# weatherstation.net
KiCad netlist of a schematic drawn in Altium Designer
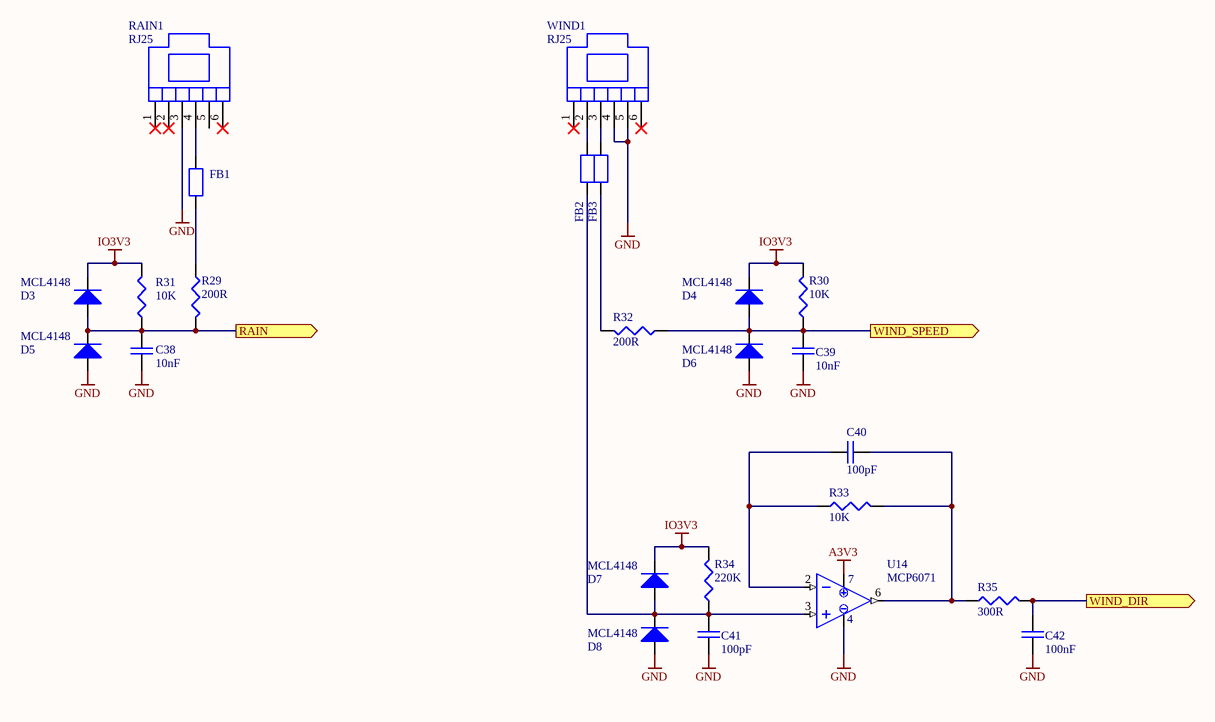
[diagram p0: weatherstation.SchDoc]

(export (version "E")
  (design (tool "Eeschema 10.0.6"))
  (components
    (comp (ref "C38")
      (value "10nF")
      (footprint "0603")
      (description "Capacitor")
      (fields (field (name "OWNER") "Nuno Brum"))
      (libsource (lib "Alcetronics_Devices") (part "CAP"))
    )
    (comp (ref "C39")
      (value "10nF")
      (footprint "0603")
      (description "Capacitor")
      (fields (field (name "OWNER") "Nuno Brum"))
      (libsource (lib "Alcetronics_Devices") (part "CAP"))
    )
    (comp (ref "C40")
      (value "100pF")
      (footprint "0603")
      (description "Capacitor")
      (fields (field (name "OWNER") "Nuno Brum"))
      (libsource (lib "Alcetronics_Devices") (part "CAP"))
    )
    (comp (ref "C41")
      (value "100pF")
      (footprint "0603")
      (description "Capacitor")
      (fields (field (name "OWNER") "Nuno Brum"))
      (libsource (lib "Alcetronics_Devices") (part "CAP"))
    )
    (comp (ref "C42")
      (value "100nF")
      (footprint "0603")
      (description "Capacitor")
      (fields (field (name "OWNER") "Nuno Brum"))
      (libsource (lib "Alcetronics_Devices") (part "CAP"))
    )
    (comp (ref "D3")
      (value "MCL4148")
      (footprint "0805@DIODE")
      (description "Vishay Standard Avalanche Sinterglass Diode")
      (fields (field (name "OWNER") "Nuno Brum"))
      (libsource (lib "Alcetronics_Devices") (part "Diode"))
    )
    (comp (ref "D4")
      (value "MCL4148")
      (footprint "0805@DIODE")
      (description "Vishay Standard Avalanche Sinterglass Diode")
      (fields (field (name "OWNER") "Nuno Brum"))
      (libsource (lib "Alcetronics_Devices") (part "Diode"))
    )
    (comp (ref "D5")
      (value "MCL4148")
      (footprint "0805@DIODE")
      (description "Vishay Standard Avalanche Sinterglass Diode")
      (fields (field (name "OWNER") "Nuno Brum"))
      (libsource (lib "Alcetronics_Devices") (part "Diode"))
    )
    (comp (ref "D6")
      (value "MCL4148")
      (footprint "0805@DIODE")
      (description "Vishay Standard Avalanche Sinterglass Diode")
      (fields (field (name "OWNER") "Nuno Brum"))
      (libsource (lib "Alcetronics_Devices") (part "Diode"))
    )
    (comp (ref "D7")
      (value "MCL4148")
      (footprint "0805@DIODE")
      (description "Vishay Standard Avalanche Sinterglass Diode")
      (fields (field (name "OWNER") "Nuno Brum"))
      (libsource (lib "Alcetronics_Devices") (part "Diode"))
    )
    (comp (ref "D8")
      (value "MCL4148")
      (footprint "0805@DIODE")
      (description "Vishay Standard Avalanche Sinterglass Diode")
      (fields (field (name "OWNER") "Nuno Brum"))
      (libsource (lib "Alcetronics_Devices") (part "Diode"))
    )
    (comp (ref "FB1")
      (value "150Z_100MHz")
      (footprint "0805")
      (description "Ferrite bead")
      (fields (field (name "OWNER") "Sergio Pires"))
      (libsource (lib "Alcetronics_Devices") (part "FERRITE-BEAD-AXIAL"))
    )
    (comp (ref "FB2")
      (value "150Z_100MHz")
      (footprint "0805")
      (description "Ferrite bead")
      (fields (field (name "OWNER") "Sergio Pires"))
      (libsource (lib "Alcetronics_Devices") (part "FERRITE-BEAD-AXIAL"))
    )
    (comp (ref "FB3")
      (value "150Z_100MHz")
      (footprint "0805")
      (description "Ferrite bead")
      (fields (field (name "OWNER") "Sergio Pires"))
      (libsource (lib "Alcetronics_Devices") (part "FERRITE-BEAD-AXIAL"))
    )
    (comp (ref "R29")
      (value "200R")
      (footprint "0603")
      (description "Resistor")
      (fields (field (name "OWNER") "Nuno Brum"))
      (libsource (lib "Alcetronics_Devices") (part "RES"))
    )
    (comp (ref "R30")
      (value "10K")
      (footprint "0603")
      (description "Resistor")
      (fields (field (name "OWNER") "Nuno Brum"))
      (libsource (lib "Alcetronics_Devices") (part "RES"))
    )
    (comp (ref "R31")
      (value "10K")
      (footprint "0603")
      (description "Resistor")
      (fields (field (name "OWNER") "Nuno Brum"))
      (libsource (lib "Alcetronics_Devices") (part "RES"))
    )
    (comp (ref "R32")
      (value "200R")
      (footprint "0603")
      (description "Resistor")
      (fields (field (name "OWNER") "Nuno Brum"))
      (libsource (lib "Alcetronics_Devices") (part "RES"))
    )
    (comp (ref "R33")
      (value "10K")
      (footprint "0603")
      (description "Resistor")
      (fields (field (name "OWNER") "Nuno Brum"))
      (libsource (lib "Alcetronics_Devices") (part "RES"))
    )
    (comp (ref "R34")
      (value "220K")
      (footprint "0603")
      (description "Resistor")
      (fields (field (name "OWNER") "Nuno Brum"))
      (libsource (lib "Alcetronics_Devices") (part "RES"))
    )
    (comp (ref "R35")
      (value "300R")
      (footprint "0603")
      (description "Resistor")
      (fields (field (name "OWNER") "Nuno Brum"))
      (libsource (lib "Alcetronics_Devices") (part "RES"))
    )
    (comp (ref "RAIN1")
      (value "RJ25")
      (footprint "RJ25")
      (description "RJ25 Connector")
      (libsource (lib "Alcetronics_EM") (part "RJ25"))
    )
    (comp (ref "U14")
      (value "MCP6071")
      (footprint "SOIC-8")
      (description "Low-Offset Opamp")
      (libsource (lib "Alcetronics_IC") (part "MCP6V26"))
    )
    (comp (ref "WIND1")
      (value "RJ25")
      (footprint "RJ25")
      (description "RJ25 Connector")
      (libsource (lib "Alcetronics_EM") (part "RJ25"))
    )
  )
  (nets
    (net (code "1") (name "/RAIN") (class "Default")
      (node (ref "C38") (pin "2") (pinfunction "2_2") (pintype "passive"))
      (node (ref "D3") (pin "A") (pinfunction "A_A") (pintype "passive"))
      (node (ref "D5") (pin "K") (pinfunction "K_K") (pintype "passive"))
      (node (ref "R29") (pin "2") (pinfunction "2_2") (pintype "passive"))
      (node (ref "R31") (pin "1") (pinfunction "1_1") (pintype "passive"))
    )
    (net (code "2") (name "/WIND_DIR") (class "Default")
      (node (ref "C42") (pin "2") (pinfunction "2_2") (pintype "passive"))
      (node (ref "R35") (pin "2") (pinfunction "2_2") (pintype "passive"))
    )
    (net (code "3") (name "/WIND_SPEED") (class "Default")
      (node (ref "C39") (pin "2") (pinfunction "2_2") (pintype "passive"))
      (node (ref "D4") (pin "A") (pinfunction "A_A") (pintype "passive"))
      (node (ref "D6") (pin "K") (pinfunction "K_K") (pintype "passive"))
      (node (ref "R30") (pin "1") (pinfunction "1_1") (pintype "passive"))
      (node (ref "R32") (pin "1") (pinfunction "1_1") (pintype "passive"))
    )
    (net (code "4") (name "A3V3") (class "Default")
      (node (ref "U14") (pin "7") (pinfunction "VDD_7") (pintype "power_in"))
    )
    (net (code "5") (name "GND") (class "Default")
      (node (ref "C38") (pin "1") (pinfunction "1_1") (pintype "passive"))
      (node (ref "C39") (pin "1") (pinfunction "1_1") (pintype "passive"))
      (node (ref "C41") (pin "1") (pinfunction "1_1") (pintype "passive"))
      (node (ref "C42") (pin "1") (pinfunction "1_1") (pintype "passive"))
      (node (ref "D5") (pin "A") (pinfunction "A_A") (pintype "passive"))
      (node (ref "D6") (pin "A") (pinfunction "A_A") (pintype "passive"))
      (node (ref "D8") (pin "A") (pinfunction "A_A") (pintype "passive"))
      (node (ref "RAIN1") (pin "3") (pinfunction "3_3") (pintype "passive"))
      (node (ref "U14") (pin "4") (pinfunction "VSS_4") (pintype "power_in"))
      (node (ref "WIND1") (pin "4") (pinfunction "4_4") (pintype "passive"))
      (node (ref "WIND1") (pin "5") (pinfunction "5_5") (pintype "passive"))
    )
    (net (code "6") (name "IO3V3") (class "Default")
      (node (ref "D3") (pin "K") (pinfunction "K_K") (pintype "passive"))
      (node (ref "D4") (pin "K") (pinfunction "K_K") (pintype "passive"))
      (node (ref "D7") (pin "K") (pinfunction "K_K") (pintype "passive"))
      (node (ref "R30") (pin "2") (pinfunction "2_2") (pintype "passive"))
      (node (ref "R31") (pin "2") (pinfunction "2_2") (pintype "passive"))
      (node (ref "R34") (pin "2") (pinfunction "2_2") (pintype "passive"))
    )
    (net (code "7") (name "Net-(FB1-Pad1)") (class "Default")
      (node (ref "FB1") (pin "1") (pinfunction "1_1") (pintype "passive"))
      (node (ref "R29") (pin "1") (pinfunction "1_1") (pintype "passive"))
    )
    (net (code "8") (name "Net-(FB1-Pad2)") (class "Default")
      (node (ref "FB1") (pin "2") (pinfunction "2_2") (pintype "passive"))
      (node (ref "RAIN1") (pin "4") (pinfunction "4_4") (pintype "passive"))
    )
    (net (code "9") (name "Net-(FB2-Pad1)") (class "Default")
      (node (ref "FB2") (pin "1") (pinfunction "1_1") (pintype "passive"))
      (node (ref "WIND1") (pin "2") (pinfunction "2_2") (pintype "passive"))
    )
    (net (code "10") (name "Net-(FB3-Pad1)") (class "Default")
      (node (ref "FB3") (pin "1") (pinfunction "1_1") (pintype "passive"))
      (node (ref "WIND1") (pin "3") (pinfunction "3_3") (pintype "passive"))
    )
    (net (code "11") (name "Net-(FB3-Pad2)") (class "Default")
      (node (ref "FB3") (pin "2") (pinfunction "2_2") (pintype "passive"))
      (node (ref "R32") (pin "2") (pinfunction "2_2") (pintype "passive"))
    )
    (net (code "12") (name "Net-(U14-INN)") (class "Default")
      (node (ref "C40") (pin "1") (pinfunction "1_1") (pintype "passive"))
      (node (ref "R33") (pin "1") (pinfunction "1_1") (pintype "passive"))
      (node (ref "U14") (pin "2") (pinfunction "INN_2") (pintype "input"))
    )
    (net (code "13") (name "Net-(U14-INP)") (class "Default")
      (node (ref "C41") (pin "2") (pinfunction "2_2") (pintype "passive"))
      (node (ref "D7") (pin "A") (pinfunction "A_A") (pintype "passive"))
      (node (ref "D8") (pin "K") (pinfunction "K_K") (pintype "passive"))
      (node (ref "FB2") (pin "2") (pinfunction "2_2") (pintype "passive"))
      (node (ref "R34") (pin "1") (pinfunction "1_1") (pintype "passive"))
      (node (ref "U14") (pin "3") (pinfunction "INP_3") (pintype "input"))
    )
    (net (code "14") (name "Net-(U14-VOUT)") (class "Default")
      (node (ref "C40") (pin "2") (pinfunction "2_2") (pintype "passive"))
      (node (ref "R33") (pin "2") (pinfunction "2_2") (pintype "passive"))
      (node (ref "R35") (pin "1") (pinfunction "1_1") (pintype "passive"))
      (node (ref "U14") (pin "6") (pinfunction "VOUT_6") (pintype "output"))
    )
    (net (code "15") (name "unconnected-(RAIN1-Pad1)") (class "Default")
      (node (ref "RAIN1") (pin "1") (pinfunction "1_1") (pintype "passive+no_connect"))
    )
    (net (code "16") (name "unconnected-(RAIN1-Pad2)") (class "Default")
      (node (ref "RAIN1") (pin "2") (pinfunction "2_2") (pintype "passive+no_connect"))
    )
    (net (code "17") (name "unconnected-(RAIN1-Pad5)") (class "Default")
      (node (ref "RAIN1") (pin "5") (pinfunction "5_5") (pintype "passive"))
    )
    (net (code "18") (name "unconnected-(RAIN1-Pad6)") (class "Default")
      (node (ref "RAIN1") (pin "6") (pinfunction "6_6") (pintype "passive+no_connect"))
    )
    (net (code "19") (name "unconnected-(WIND1-Pad1)") (class "Default")
      (node (ref "WIND1") (pin "1") (pinfunction "1_1") (pintype "passive+no_connect"))
    )
    (net (code "20") (name "unconnected-(WIND1-Pad6)") (class "Default")
      (node (ref "WIND1") (pin "6") (pinfunction "6_6") (pintype "passive+no_connect"))
    )
  )
)
